# Kocka_BDD.net
KiCad netlist of a schematic drawn in Altium Designer
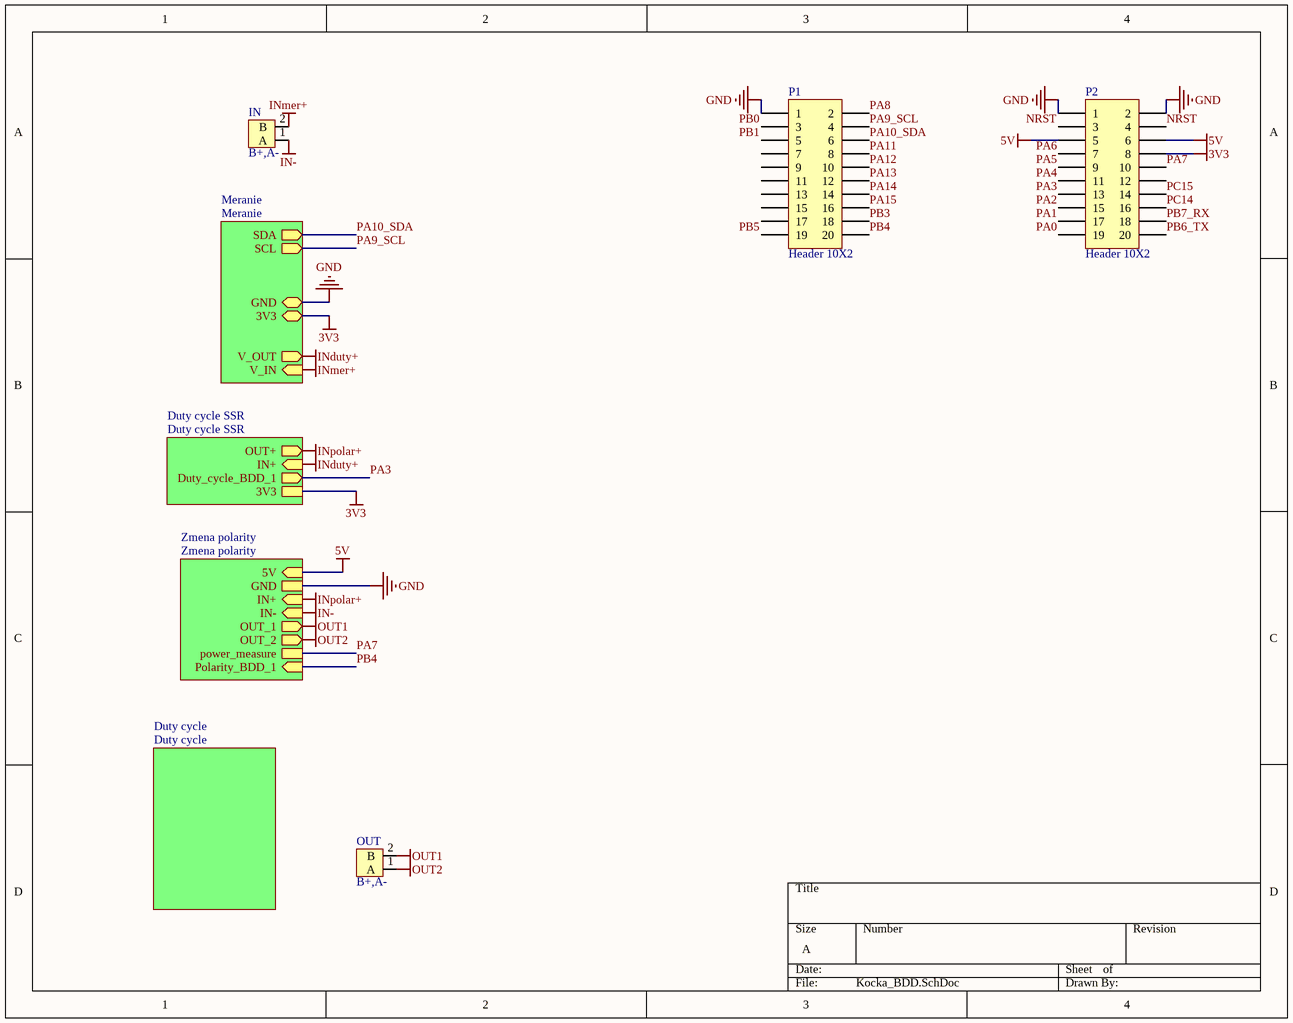
[diagram p0: Kocka_BDD.SchDoc]

(export (version "E")
  (design (tool "Eeschema 10.0.6"))
  (components
    (comp (ref "IN")
      (value "B+,A-")
      (footprint "CON_2CH_PLUG")
      (description "TBG-5.0-KW-2P")
      (libsource (lib "SCH_Aquatec") (part "CON_2CH_PLUG"))
    )
    (comp (ref "OUT")
      (value "B+,A-")
      (footprint "CON_2CH_PLUG")
      (description "TBG-5.0-KW-2P")
      (libsource (lib "SCH_Aquatec") (part "CON_2CH_PLUG"))
    )
    (comp (ref "P1")
      (value "Header 10X2")
      (footprint "HDR2X10")
      (description "Header, 10-Pin, Dual row")
      (fields (field (name "PUBLISHER") "Altium Limited"))
      (libsource (lib "Miscellaneous Connectors") (part "Header 10X2"))
    )
    (comp (ref "P2")
      (value "Header 10X2")
      (footprint "HDR2X10")
      (description "Header, 10-Pin, Dual row")
      (fields (field (name "PUBLISHER") "Altium Limited"))
      (libsource (lib "Miscellaneous Connectors") (part "Header 10X2"))
    )
  )
  (nets
    (net (code "1") (name "/NRST") (class "Default")
      (node (ref "P2") (pin "3") (pinfunction "3_3") (pintype "passive"))
      (node (ref "P2") (pin "4") (pinfunction "4_4") (pintype "passive"))
    )
    (net (code "2") (name "/PA0") (class "Default")
      (node (ref "P2") (pin "19") (pinfunction "19_19") (pintype "passive"))
    )
    (net (code "3") (name "/PA1") (class "Default")
      (node (ref "P2") (pin "17") (pinfunction "17_17") (pintype "passive"))
    )
    (net (code "4") (name "/PA2") (class "Default")
      (node (ref "P2") (pin "15") (pinfunction "15_15") (pintype "passive"))
    )
    (net (code "5") (name "/PA3") (class "Default")
      (node (ref "P2") (pin "13") (pinfunction "13_13") (pintype "passive"))
    )
    (net (code "6") (name "/PA4") (class "Default")
      (node (ref "P2") (pin "11") (pinfunction "11_11") (pintype "passive"))
    )
    (net (code "7") (name "/PA5") (class "Default")
      (node (ref "P2") (pin "9") (pinfunction "9_9") (pintype "passive"))
    )
    (net (code "8") (name "/PA6") (class "Default")
      (node (ref "P2") (pin "7") (pinfunction "7_7") (pintype "passive"))
    )
    (net (code "9") (name "/PA7") (class "Default")
      (node (ref "P2") (pin "10") (pinfunction "10_10") (pintype "passive"))
    )
    (net (code "10") (name "/PA8") (class "Default")
      (node (ref "P1") (pin "2") (pinfunction "2_2") (pintype "passive"))
    )
    (net (code "11") (name "/PA9_SCL") (class "Default")
      (node (ref "P1") (pin "4") (pinfunction "4_4") (pintype "passive"))
    )
    (net (code "12") (name "/PA10_SDA") (class "Default")
      (node (ref "P1") (pin "6") (pinfunction "6_6") (pintype "passive"))
    )
    (net (code "13") (name "/PA11") (class "Default")
      (node (ref "P1") (pin "8") (pinfunction "8_8") (pintype "passive"))
    )
    (net (code "14") (name "/PA12") (class "Default")
      (node (ref "P1") (pin "10") (pinfunction "10_10") (pintype "passive"))
    )
    (net (code "15") (name "/PA13") (class "Default")
      (node (ref "P1") (pin "12") (pinfunction "12_12") (pintype "passive"))
    )
    (net (code "16") (name "/PA14") (class "Default")
      (node (ref "P1") (pin "14") (pinfunction "14_14") (pintype "passive"))
    )
    (net (code "17") (name "/PA15") (class "Default")
      (node (ref "P1") (pin "16") (pinfunction "16_16") (pintype "passive"))
    )
    (net (code "18") (name "/PB0") (class "Default")
      (node (ref "P1") (pin "3") (pinfunction "3_3") (pintype "passive"))
    )
    (net (code "19") (name "/PB1") (class "Default")
      (node (ref "P1") (pin "5") (pinfunction "5_5") (pintype "passive"))
    )
    (net (code "20") (name "/PB3") (class "Default")
      (node (ref "P1") (pin "18") (pinfunction "18_18") (pintype "passive"))
    )
    (net (code "21") (name "/PB4") (class "Default")
      (node (ref "P1") (pin "20") (pinfunction "20_20") (pintype "passive"))
    )
    (net (code "22") (name "/PB5") (class "Default")
      (node (ref "P1") (pin "19") (pinfunction "19_19") (pintype "passive"))
    )
    (net (code "23") (name "/PB6_TX") (class "Default")
      (node (ref "P2") (pin "20") (pinfunction "20_20") (pintype "passive"))
    )
    (net (code "24") (name "/PB7_RX") (class "Default")
      (node (ref "P2") (pin "18") (pinfunction "18_18") (pintype "passive"))
    )
    (net (code "25") (name "/PC14") (class "Default")
      (node (ref "P2") (pin "16") (pinfunction "16_16") (pintype "passive"))
    )
    (net (code "26") (name "/PC15") (class "Default")
      (node (ref "P2") (pin "14") (pinfunction "14_14") (pintype "passive"))
    )
    (net (code "27") (name "3V3") (class "Default")
      (node (ref "P2") (pin "8") (pinfunction "8_8") (pintype "passive"))
    )
    (net (code "28") (name "5V") (class "Default")
      (node (ref "P2") (pin "5") (pinfunction "5_5") (pintype "passive"))
      (node (ref "P2") (pin "6") (pinfunction "6_6") (pintype "passive"))
    )
    (net (code "29") (name "GND") (class "Default")
      (node (ref "P1") (pin "1") (pinfunction "1_1") (pintype "passive"))
      (node (ref "P2") (pin "1") (pinfunction "1_1") (pintype "passive"))
      (node (ref "P2") (pin "2") (pinfunction "2_2") (pintype "passive"))
    )
    (net (code "30") (name "IN-") (class "Default")
      (node (ref "IN") (pin "1") (pinfunction "A_1") (pintype "passive"))
    )
    (net (code "32") (name "INmer+") (class "Default")
      (node (ref "IN") (pin "2") (pinfunction "B_2") (pintype "passive"))
    )
    (net (code "34") (name "OUT1") (class "Default")
      (node (ref "OUT") (pin "2") (pinfunction "B_2") (pintype "passive"))
    )
    (net (code "35") (name "OUT2") (class "Default")
      (node (ref "OUT") (pin "1") (pinfunction "A_1") (pintype "passive"))
    )
    (net (code "36") (name "unconnected-(P1-Pad7)") (class "Default")
      (node (ref "P1") (pin "7") (pinfunction "7_7") (pintype "passive"))
    )
    (net (code "37") (name "unconnected-(P1-Pad9)") (class "Default")
      (node (ref "P1") (pin "9") (pinfunction "9_9") (pintype "passive"))
    )
    (net (code "38") (name "unconnected-(P1-Pad11)") (class "Default")
      (node (ref "P1") (pin "11") (pinfunction "11_11") (pintype "passive"))
    )
    (net (code "39") (name "unconnected-(P1-Pad13)") (class "Default")
      (node (ref "P1") (pin "13") (pinfunction "13_13") (pintype "passive"))
    )
    (net (code "40") (name "unconnected-(P1-Pad15)") (class "Default")
      (node (ref "P1") (pin "15") (pinfunction "15_15") (pintype "passive"))
    )
    (net (code "41") (name "unconnected-(P1-Pad17)") (class "Default")
      (node (ref "P1") (pin "17") (pinfunction "17_17") (pintype "passive"))
    )
    (net (code "42") (name "unconnected-(P2-Pad12)") (class "Default")
      (node (ref "P2") (pin "12") (pinfunction "12_12") (pintype "passive"))
    )
  )
)
